# echo.net
KiCad netlist of a schematic drawn in EasyEDA
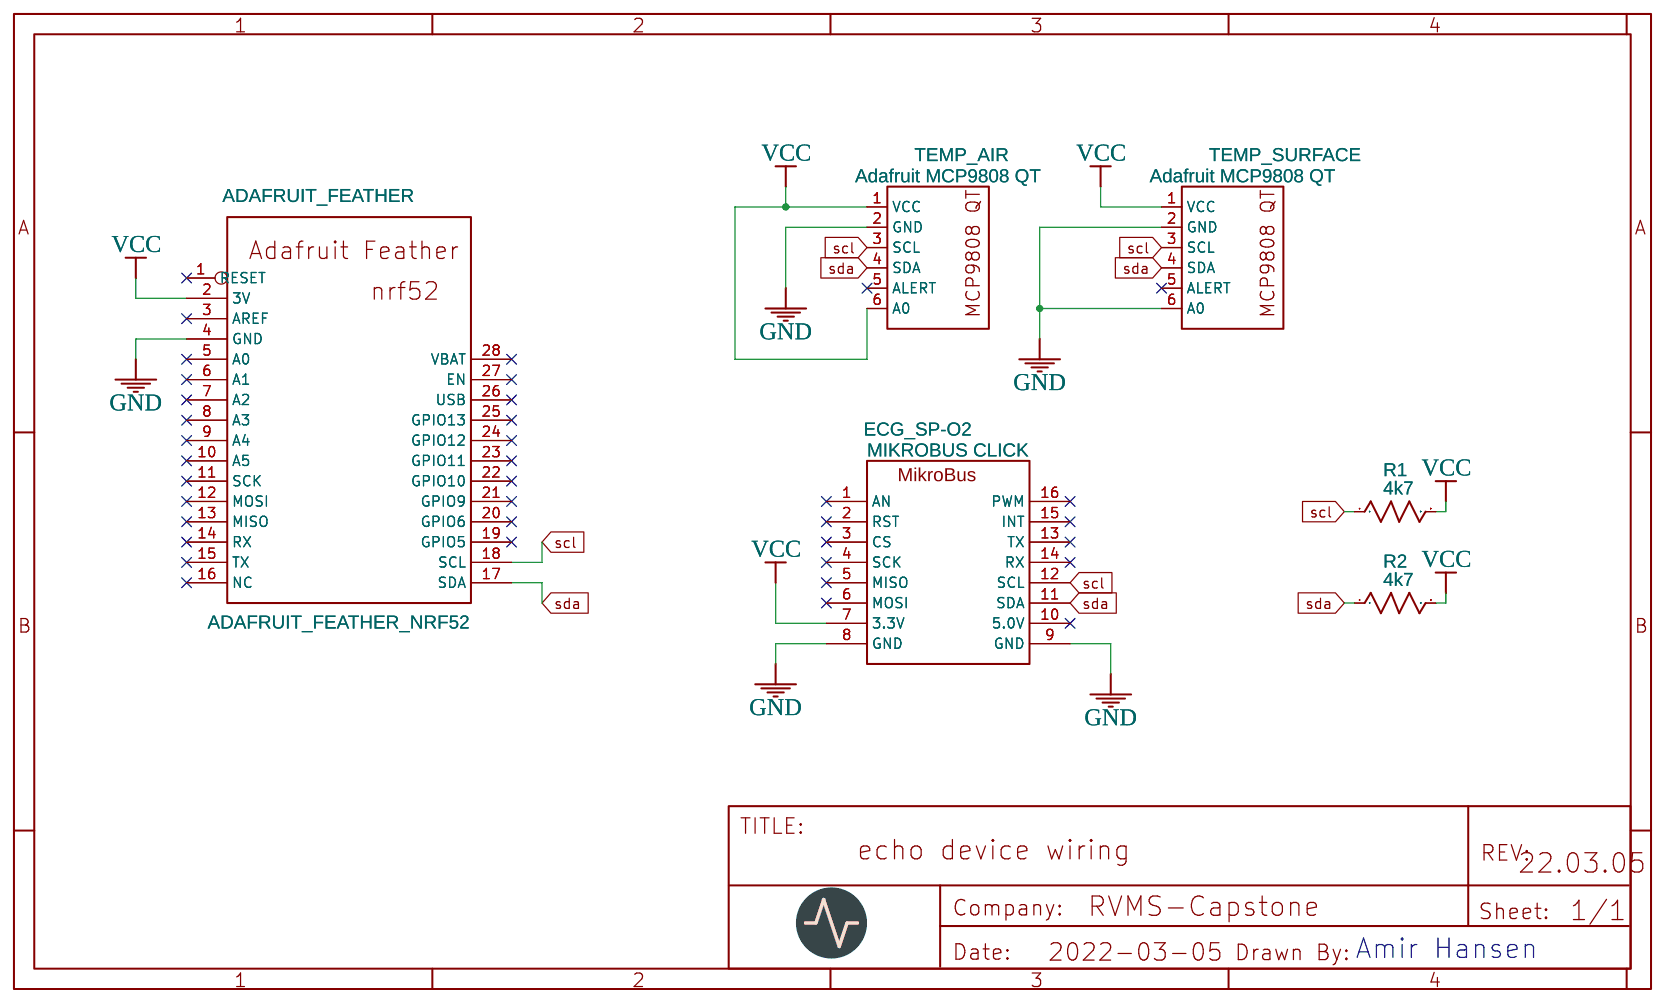
[diagram p0: schematic sheet]

(export (version "E")
  (design (tool "Eeschema 10.0.6"))
  (components
    (comp (ref "ADAFRUIT_FEATHER")
      (value "ADAFRUIT_FEATHER_NRF52")
      (libsource (lib "") (part "Adafruit Feather nrf52"))
    )
    (comp (ref "ECG_SP-O2") (value "MIKROBUS CLICK") (libsource (lib "") (part "MIKROBUS CLICK")))
    (comp (ref "R1") (value "4k7") (libsource (lib "") (part "R_AXIAL-0.3_US")))
    (comp (ref "R2") (value "4k7") (libsource (lib "") (part "R_AXIAL-0.3_US")))
    (comp (ref "TEMP_AIR") (value "Adafruit MCP9808 QT") (libsource (lib "") (part "Adafruit MCP9808 QT")))
    (comp (ref "TEMP_SURFACE")
      (value "Adafruit MCP9808 QT")
      (libsource (lib "") (part "Adafruit MCP9808 QT_1"))
    )
  )
  (nets
    (net (code "1") (name "GND") (class "Default")
      (node (ref "ADAFRUIT_FEATHER") (pin "4") (pinfunction "GND_4") (pintype "unspecified"))
      (node (ref "ECG_SP-O2") (pin "8") (pinfunction "GND_8") (pintype "passive"))
      (node (ref "ECG_SP-O2") (pin "9") (pinfunction "GND_9") (pintype "passive"))
      (node (ref "TEMP_AIR") (pin "2") (pinfunction "GND_2") (pintype "passive"))
      (node (ref "TEMP_SURFACE") (pin "2") (pinfunction "GND_2") (pintype "passive"))
      (node (ref "TEMP_SURFACE") (pin "6") (pinfunction "A0_6") (pintype "unspecified"))
    )
    (net (code "2") (name "VCC") (class "Default")
      (node (ref "ADAFRUIT_FEATHER") (pin "2") (pinfunction "3V_2") (pintype "unspecified"))
      (node (ref "ECG_SP-O2") (pin "7") (pinfunction "3.3V_7") (pintype "passive"))
      (node (ref "R1") (pin "2") (pinfunction "2_2") (pintype "unspecified"))
      (node (ref "R2") (pin "2") (pinfunction "2_2") (pintype "unspecified"))
      (node (ref "TEMP_AIR") (pin "1") (pinfunction "VCC_1") (pintype "passive"))
      (node (ref "TEMP_AIR") (pin "6") (pinfunction "A0_6") (pintype "unspecified"))
      (node (ref "TEMP_SURFACE") (pin "1") (pinfunction "VCC_1") (pintype "passive"))
    )
    (net (code "3") (name "scl") (class "Default")
      (node (ref "ADAFRUIT_FEATHER") (pin "18") (pinfunction "SCL_18") (pintype "unspecified"))
      (node (ref "ECG_SP-O2") (pin "12") (pinfunction "SCL_12") (pintype "unspecified"))
      (node (ref "R1") (pin "1") (pinfunction "1_1") (pintype "unspecified"))
      (node (ref "TEMP_AIR") (pin "3") (pinfunction "SCL_3") (pintype "bidirectional"))
      (node (ref "TEMP_SURFACE") (pin "3") (pinfunction "SCL_3") (pintype "bidirectional"))
    )
    (net (code "4") (name "sda") (class "Default")
      (node (ref "ADAFRUIT_FEATHER") (pin "17") (pinfunction "SDA_17") (pintype "unspecified"))
      (node (ref "ECG_SP-O2") (pin "11") (pinfunction "SDA_11") (pintype "unspecified"))
      (node (ref "R2") (pin "1") (pinfunction "1_1") (pintype "unspecified"))
      (node (ref "TEMP_AIR") (pin "4") (pinfunction "SDA_4") (pintype "bidirectional"))
      (node (ref "TEMP_SURFACE") (pin "4") (pinfunction "SDA_4") (pintype "bidirectional"))
    )
    (net (code "5") (name "unconnected-(ADAFRUIT_FEATHER-A0-Pad5)") (class "Default")
      (node (ref "ADAFRUIT_FEATHER") (pin "5") (pinfunction "A0_5") (pintype "unspecified+no_connect"))
    )
    (net (code "6") (name "unconnected-(ADAFRUIT_FEATHER-A1-Pad6)") (class "Default")
      (node (ref "ADAFRUIT_FEATHER") (pin "6") (pinfunction "A1_6") (pintype "unspecified+no_connect"))
    )
    (net (code "7") (name "unconnected-(ADAFRUIT_FEATHER-A2-Pad7)") (class "Default")
      (node (ref "ADAFRUIT_FEATHER") (pin "7") (pinfunction "A2_7") (pintype "unspecified+no_connect"))
    )
    (net (code "8") (name "unconnected-(ADAFRUIT_FEATHER-A3-Pad8)") (class "Default")
      (node (ref "ADAFRUIT_FEATHER") (pin "8") (pinfunction "A3_8") (pintype "unspecified+no_connect"))
    )
    (net (code "9") (name "unconnected-(ADAFRUIT_FEATHER-A4-Pad9)") (class "Default")
      (node (ref "ADAFRUIT_FEATHER") (pin "9") (pinfunction "A4_9") (pintype "unspecified+no_connect"))
    )
    (net (code "10") (name "unconnected-(ADAFRUIT_FEATHER-A5-Pad10)") (class "Default")
      (node (ref "ADAFRUIT_FEATHER") (pin "10") (pinfunction "A5_10") (pintype "unspecified+no_connect"))
    )
    (net (code "11") (name "unconnected-(ADAFRUIT_FEATHER-AREF-Pad3)") (class "Default")
      (node (ref "ADAFRUIT_FEATHER") (pin "3") (pinfunction "AREF_3") (pintype "unspecified+no_connect"))
    )
    (net (code "12") (name "unconnected-(ADAFRUIT_FEATHER-EN-Pad27)") (class "Default")
      (node (ref "ADAFRUIT_FEATHER") (pin "27") (pinfunction "EN_27") (pintype "unspecified+no_connect"))
    )
    (net (code "13") (name "unconnected-(ADAFRUIT_FEATHER-GPIO5-Pad19)") (class "Default")
      (node (ref "ADAFRUIT_FEATHER") (pin "19") (pinfunction "GPIO5_19") (pintype "unspecified+no_connect"))
    )
    (net (code "14") (name "unconnected-(ADAFRUIT_FEATHER-GPIO6-Pad20)") (class "Default")
      (node (ref "ADAFRUIT_FEATHER") (pin "20") (pinfunction "GPIO6_20") (pintype "unspecified+no_connect"))
    )
    (net (code "15") (name "unconnected-(ADAFRUIT_FEATHER-GPIO9-Pad21)") (class "Default")
      (node (ref "ADAFRUIT_FEATHER") (pin "21") (pinfunction "GPIO9_21") (pintype "unspecified+no_connect"))
    )
    (net (code "16") (name "unconnected-(ADAFRUIT_FEATHER-GPIO10-Pad22)") (class "Default")
      (node (ref "ADAFRUIT_FEATHER") (pin "22") (pinfunction "GPIO10_22") (pintype "unspecified+no_connect"))
    )
    (net (code "17") (name "unconnected-(ADAFRUIT_FEATHER-GPIO11-Pad23)") (class "Default")
      (node (ref "ADAFRUIT_FEATHER") (pin "23") (pinfunction "GPIO11_23") (pintype "unspecified+no_connect"))
    )
    (net (code "18") (name "unconnected-(ADAFRUIT_FEATHER-GPIO12-Pad24)") (class "Default")
      (node (ref "ADAFRUIT_FEATHER") (pin "24") (pinfunction "GPIO12_24") (pintype "unspecified+no_connect"))
    )
    (net (code "19") (name "unconnected-(ADAFRUIT_FEATHER-GPIO13-Pad25)") (class "Default")
      (node (ref "ADAFRUIT_FEATHER") (pin "25") (pinfunction "GPIO13_25") (pintype "unspecified+no_connect"))
    )
    (net (code "20") (name "unconnected-(ADAFRUIT_FEATHER-MISO-Pad13)") (class "Default")
      (node (ref "ADAFRUIT_FEATHER") (pin "13") (pinfunction "MISO_13") (pintype "unspecified+no_connect"))
    )
    (net (code "21") (name "unconnected-(ADAFRUIT_FEATHER-MOSI-Pad12)") (class "Default")
      (node (ref "ADAFRUIT_FEATHER") (pin "12") (pinfunction "MOSI_12") (pintype "unspecified+no_connect"))
    )
    (net (code "22") (name "unconnected-(ADAFRUIT_FEATHER-NC-Pad16)") (class "Default")
      (node (ref "ADAFRUIT_FEATHER") (pin "16") (pinfunction "NC_16") (pintype "unspecified+no_connect"))
    )
    (net (code "23") (name "unconnected-(ADAFRUIT_FEATHER-RESET-Pad1)") (class "Default")
      (node (ref "ADAFRUIT_FEATHER") (pin "1") (pinfunction "RESET_1") (pintype "unspecified+no_connect"))
    )
    (net (code "24") (name "unconnected-(ADAFRUIT_FEATHER-RX-Pad14)") (class "Default")
      (node (ref "ADAFRUIT_FEATHER") (pin "14") (pinfunction "RX_14") (pintype "unspecified+no_connect"))
    )
    (net (code "25") (name "unconnected-(ADAFRUIT_FEATHER-SCK-Pad11)") (class "Default")
      (node (ref "ADAFRUIT_FEATHER") (pin "11") (pinfunction "SCK_11") (pintype "unspecified+no_connect"))
    )
    (net (code "26") (name "unconnected-(ADAFRUIT_FEATHER-TX-Pad15)") (class "Default")
      (node (ref "ADAFRUIT_FEATHER") (pin "15") (pinfunction "TX_15") (pintype "unspecified+no_connect"))
    )
    (net (code "27") (name "unconnected-(ADAFRUIT_FEATHER-USB-Pad26)") (class "Default")
      (node (ref "ADAFRUIT_FEATHER") (pin "26") (pinfunction "USB_26") (pintype "unspecified+no_connect"))
    )
    (net (code "28") (name "unconnected-(ADAFRUIT_FEATHER-VBAT-Pad28)") (class "Default")
      (node (ref "ADAFRUIT_FEATHER") (pin "28") (pinfunction "VBAT_28") (pintype "unspecified+no_connect"))
    )
    (net (code "29") (name "unconnected-(ECG_SP-O2-5.0V-Pad10)") (class "Default")
      (node (ref "ECG_SP-O2") (pin "10") (pinfunction "5.0V_10") (pintype "passive+no_connect"))
    )
    (net (code "30") (name "unconnected-(ECG_SP-O2-AN-Pad1)") (class "Default")
      (node (ref "ECG_SP-O2") (pin "1") (pinfunction "AN_1") (pintype "unspecified+no_connect"))
    )
    (net (code "31") (name "unconnected-(ECG_SP-O2-CS-Pad3)") (class "Default")
      (node (ref "ECG_SP-O2") (pin "3") (pinfunction "CS_3") (pintype "unspecified+no_connect"))
    )
    (net (code "32") (name "unconnected-(ECG_SP-O2-INT-Pad15)") (class "Default")
      (node (ref "ECG_SP-O2") (pin "15") (pinfunction "INT_15") (pintype "unspecified+no_connect"))
    )
    (net (code "33") (name "unconnected-(ECG_SP-O2-MISO-Pad5)") (class "Default")
      (node (ref "ECG_SP-O2") (pin "5") (pinfunction "MISO_5") (pintype "unspecified+no_connect"))
    )
    (net (code "34") (name "unconnected-(ECG_SP-O2-MOSI-Pad6)") (class "Default")
      (node (ref "ECG_SP-O2") (pin "6") (pinfunction "MOSI_6") (pintype "unspecified+no_connect"))
    )
    (net (code "35") (name "unconnected-(ECG_SP-O2-PWM-Pad16)") (class "Default")
      (node (ref "ECG_SP-O2") (pin "16") (pinfunction "PWM_16") (pintype "unspecified+no_connect"))
    )
    (net (code "36") (name "unconnected-(ECG_SP-O2-RST-Pad2)") (class "Default")
      (node (ref "ECG_SP-O2") (pin "2") (pinfunction "RST_2") (pintype "unspecified+no_connect"))
    )
    (net (code "37") (name "unconnected-(ECG_SP-O2-RX-Pad14)") (class "Default")
      (node (ref "ECG_SP-O2") (pin "14") (pinfunction "RX_14") (pintype "unspecified+no_connect"))
    )
    (net (code "38") (name "unconnected-(ECG_SP-O2-SCK-Pad4)") (class "Default")
      (node (ref "ECG_SP-O2") (pin "4") (pinfunction "SCK_4") (pintype "unspecified+no_connect"))
    )
    (net (code "39") (name "unconnected-(ECG_SP-O2-TX-Pad13)") (class "Default")
      (node (ref "ECG_SP-O2") (pin "13") (pinfunction "TX_13") (pintype "unspecified+no_connect"))
    )
    (net (code "40") (name "unconnected-(TEMP_AIR-ALERT-Pad5)") (class "Default")
      (node (ref "TEMP_AIR") (pin "5") (pinfunction "ALERT_5") (pintype "unspecified+no_connect"))
    )
    (net (code "41") (name "unconnected-(TEMP_SURFACE-ALERT-Pad5)") (class "Default")
      (node (ref "TEMP_SURFACE") (pin "5") (pinfunction "ALERT_5") (pintype "unspecified+no_connect"))
    )
  )
)
